# main_hall.net
KiCad netlist of a schematic drawn in Altium Designer
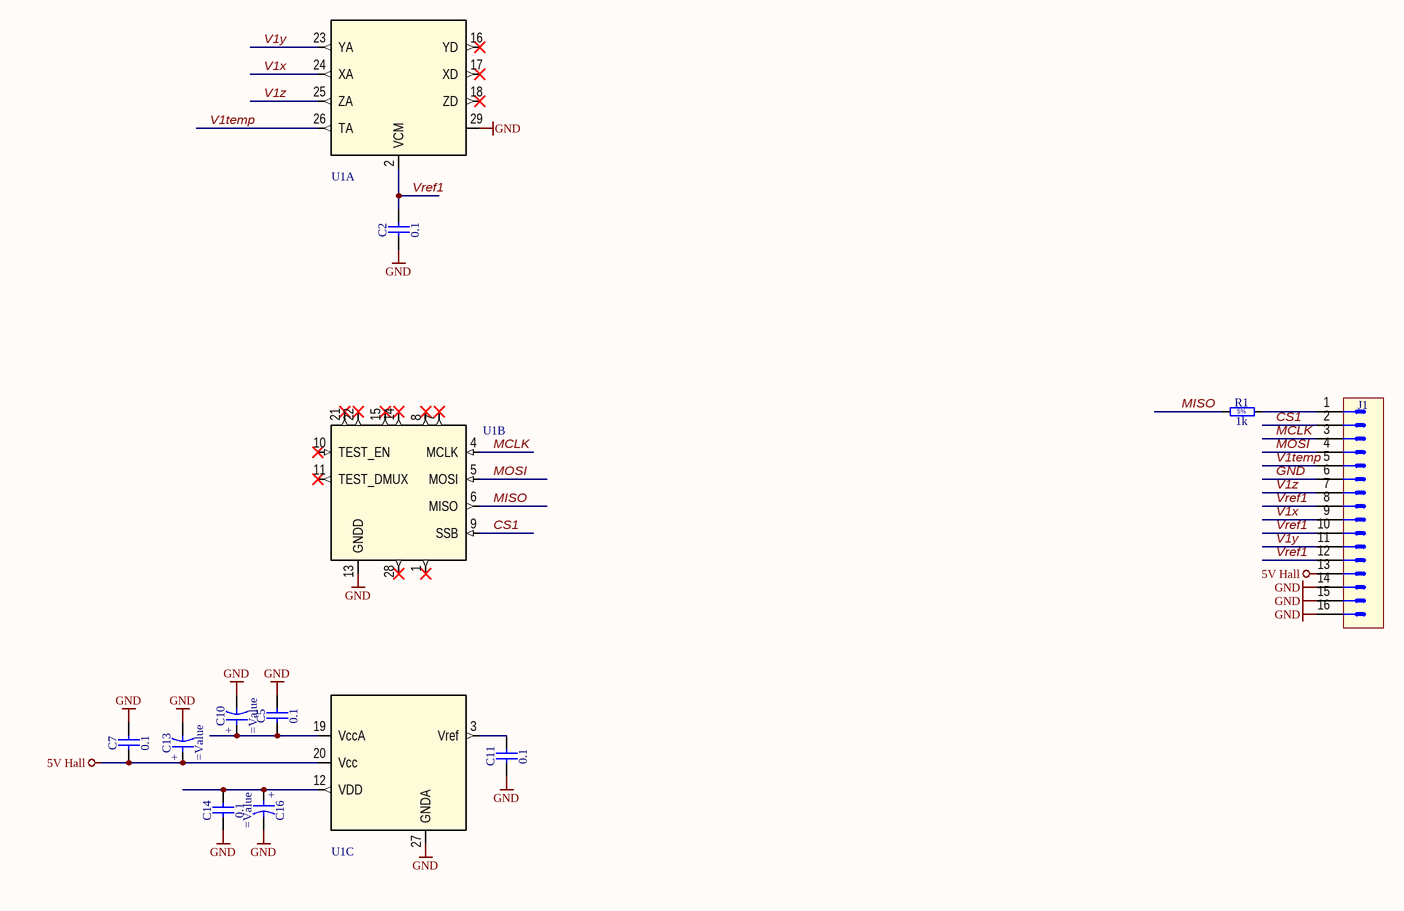
[diagram p0: main_hall.SchDoc]

(export (version "E")
  (design (tool "Eeschema 10.0.6"))
  (components
    (comp (ref "C2")
      (value "0.1")
      (footprint "CAPC3216X100N")
      (description "Non-polarised1206 capacitor")
      (libsource (lib "hall library") (part "Capacitor1206 - non polarized"))
    )
    (comp (ref "C5")
      (value "0.1")
      (footprint "CAPC3216X100N")
      (description "Non-polarised1206 capacitor")
      (libsource (lib "hall library") (part "Capacitor1206 - non polarized"))
    )
    (comp (ref "C7")
      (value "0.1")
      (footprint "CAPC3216X100N")
      (description "Non-polarised1206 capacitor")
      (libsource (lib "hall library") (part "Capacitor1206 - non polarized"))
    )
    (comp (ref "C10")
      (value "~")
      (footprint "hall library:CAPMP3528X120N")
      (description "Polarised capacitor")
      (libsource (lib "schematic_hall_library") (part "Capacitor - polarized"))
    )
    (comp (ref "C11")
      (value "0.1")
      (footprint "CAPC3216X100N")
      (description "Non-polarised1206 capacitor")
      (libsource (lib "hall library") (part "Capacitor1206 - non polarized"))
    )
    (comp (ref "C13")
      (value "~")
      (footprint "hall library:CAPMP3528X120N")
      (description "Polarised capacitor")
      (libsource (lib "schematic_hall_library") (part "Capacitor - polarized"))
    )
    (comp (ref "C14")
      (value "0.1")
      (footprint "CAPC3216X100N")
      (description "Non-polarised1206 capacitor")
      (libsource (lib "hall library") (part "Capacitor1206 - non polarized"))
    )
    (comp (ref "C16")
      (value "~")
      (footprint "hall library:CAPMP3528X120N")
      (description "Polarised capacitor")
      (libsource (lib "schematic_hall_library") (part "Capacitor - polarized"))
    )
    (comp (ref "J1")
      (value "~")
      (footprint "3M_N2516-5002RB")
      (description "Connector 16")
      (libsource (lib "hall library") (part "Connector 16"))
    )
    (comp (ref "R1")
      (value "1k")
      (footprint "footprint_hall_library:RESC2012X70N")
      (description "Resistor - 5%")
      (fields (field (name "TOLERANCE") "5%"))
      (libsource (lib "schematic_hall_library") (part "Resistor - 5%"))
    )
    (comp (ref "U1")
      (value "Hall sensor")
      (footprint "footprint_hall_library:QFN50P500X500X100-29N-S325")
      (description "SENM3Dx Vertical Hall Sensor")
      (libsource (lib "schematic_hall_library") (part "Hall sensor"))
    )
  )
  (nets
    (net (code "1") (name "/CS1") (class "Default")
      (node (ref "J1") (pin "2") (pinfunction "2_2") (pintype "passive"))
      (node (ref "U1") (pin "9") (pinfunction "SSB_9") (pintype "input"))
    )
    (net (code "2") (name "/MCLK") (class "Default")
      (node (ref "J1") (pin "3") (pinfunction "3_3") (pintype "passive"))
      (node (ref "U1") (pin "4") (pinfunction "MCLK_4") (pintype "input"))
    )
    (net (code "3") (name "/MISO") (class "Default")
      (node (ref "R1") (pin "1") (pinfunction "1_1") (pintype "passive"))
      (node (ref "U1") (pin "6") (pinfunction "MISO_6") (pintype "output"))
    )
    (net (code "4") (name "/MOSI") (class "Default")
      (node (ref "J1") (pin "4") (pinfunction "4_4") (pintype "passive"))
      (node (ref "U1") (pin "5") (pinfunction "MOSI_5") (pintype "input"))
    )
    (net (code "5") (name "/V1temp") (class "Default")
      (node (ref "J1") (pin "5") (pinfunction "5_5") (pintype "passive"))
      (node (ref "U1") (pin "26") (pinfunction "TA_26") (pintype "output"))
    )
    (net (code "6") (name "/V1x") (class "Default")
      (node (ref "J1") (pin "9") (pinfunction "9_9") (pintype "passive"))
      (node (ref "U1") (pin "24") (pinfunction "XA_24") (pintype "output"))
    )
    (net (code "7") (name "/V1y") (class "Default")
      (node (ref "J1") (pin "11") (pinfunction "11_11") (pintype "passive"))
      (node (ref "U1") (pin "23") (pinfunction "YA_23") (pintype "output"))
    )
    (net (code "8") (name "/V1z") (class "Default")
      (node (ref "J1") (pin "7") (pinfunction "7_7") (pintype "passive"))
      (node (ref "U1") (pin "25") (pinfunction "ZA_25") (pintype "output"))
    )
    (net (code "9") (name "/Vref1") (class "Default")
      (node (ref "C2") (pin "2") (pinfunction "2_2") (pintype "passive"))
      (node (ref "J1") (pin "10") (pinfunction "10_10") (pintype "passive"))
      (node (ref "J1") (pin "12") (pinfunction "12_12") (pintype "passive"))
      (node (ref "J1") (pin "8") (pinfunction "8_8") (pintype "passive"))
      (node (ref "U1") (pin "2") (pinfunction "VCM_2") (pintype "power_in"))
    )
    (net (code "10") (name "5V Hall") (class "Default")
      (node (ref "C13") (pin "1") (pinfunction "1_1") (pintype "passive"))
      (node (ref "C7") (pin "1") (pinfunction "1_1") (pintype "passive"))
      (node (ref "J1") (pin "13") (pinfunction "13_13") (pintype "passive"))
      (node (ref "U1") (pin "20") (pinfunction "Vcc_20") (pintype "power_in"))
    )
    (net (code "11") (name "GND") (class "Default")
      (node (ref "C10") (pin "2") (pinfunction "2_2") (pintype "passive"))
      (node (ref "C11") (pin "1") (pinfunction "1_1") (pintype "passive"))
      (node (ref "C13") (pin "2") (pinfunction "2_2") (pintype "passive"))
      (node (ref "C14") (pin "1") (pinfunction "1_1") (pintype "passive"))
      (node (ref "C16") (pin "2") (pinfunction "2_2") (pintype "passive"))
      (node (ref "C2") (pin "1") (pinfunction "1_1") (pintype "passive"))
      (node (ref "C5") (pin "2") (pinfunction "2_2") (pintype "passive"))
      (node (ref "C7") (pin "2") (pinfunction "2_2") (pintype "passive"))
      (node (ref "J1") (pin "14") (pinfunction "14_14") (pintype "passive"))
      (node (ref "J1") (pin "15") (pinfunction "15_15") (pintype "passive"))
      (node (ref "J1") (pin "16") (pinfunction "16_16") (pintype "passive"))
      (node (ref "J1") (pin "6") (pinfunction "6_6") (pintype "passive"))
      (node (ref "U1") (pin "13") (pinfunction "GNDD_13") (pintype "power_in"))
      (node (ref "U1") (pin "27") (pinfunction "GNDA_27") (pintype "power_in"))
      (node (ref "U1") (pin "29") (pinfunction "29_29") (pintype "passive"))
    )
    (net (code "12") (name "Net-(J1-Pad1)") (class "Default")
      (node (ref "J1") (pin "1") (pinfunction "1_1") (pintype "passive"))
      (node (ref "R1") (pin "2") (pinfunction "2_2") (pintype "passive"))
    )
    (net (code "13") (name "Net-(U1C-VDD)") (class "Default")
      (node (ref "C14") (pin "2") (pinfunction "2_2") (pintype "passive"))
      (node (ref "C16") (pin "1") (pinfunction "1_1") (pintype "passive"))
      (node (ref "U1") (pin "12") (pinfunction "VDD_12") (pintype "output"))
    )
    (net (code "14") (name "Net-(U1C-VccA)") (class "Default")
      (node (ref "C10") (pin "1") (pinfunction "1_1") (pintype "passive"))
      (node (ref "C5") (pin "1") (pinfunction "1_1") (pintype "passive"))
      (node (ref "U1") (pin "19") (pinfunction "VccA_19") (pintype "power_in"))
    )
    (net (code "15") (name "Net-(U1C-Vref)") (class "Default")
      (node (ref "C11") (pin "2") (pinfunction "2_2") (pintype "passive"))
      (node (ref "U1") (pin "3") (pinfunction "Vref_3") (pintype "output"))
    )
    (net (code "16") (name "unconnected-(U1-Pad1)") (class "Default")
      (node (ref "U1") (pin "1") (pintype "output+no_connect"))
    )
    (net (code "17") (name "unconnected-(U1-Pad7)") (class "Default")
      (node (ref "U1") (pin "7") (pintype "output+no_connect"))
    )
    (net (code "18") (name "unconnected-(U1-Pad8)") (class "Default")
      (node (ref "U1") (pin "8") (pintype "output+no_connect"))
    )
    (net (code "19") (name "unconnected-(U1-Pad14)") (class "Default")
      (node (ref "U1") (pin "14") (pintype "output+no_connect"))
    )
    (net (code "20") (name "unconnected-(U1-Pad15)") (class "Default")
      (node (ref "U1") (pin "15") (pintype "output+no_connect"))
    )
    (net (code "21") (name "unconnected-(U1-Pad21)") (class "Default")
      (node (ref "U1") (pin "21") (pintype "output+no_connect"))
    )
    (net (code "22") (name "unconnected-(U1-Pad22)") (class "Default")
      (node (ref "U1") (pin "22") (pintype "output+no_connect"))
    )
    (net (code "23") (name "unconnected-(U1-Pad28)") (class "Default")
      (node (ref "U1") (pin "28") (pintype "output+no_connect"))
    )
    (net (code "24") (name "unconnected-(U1A-XD-Pad17)") (class "Default")
      (node (ref "U1") (pin "17") (pinfunction "XD_17") (pintype "output+no_connect"))
    )
    (net (code "25") (name "unconnected-(U1A-YD-Pad16)") (class "Default")
      (node (ref "U1") (pin "16") (pinfunction "YD_16") (pintype "output+no_connect"))
    )
    (net (code "26") (name "unconnected-(U1A-ZD-Pad18)") (class "Default")
      (node (ref "U1") (pin "18") (pinfunction "ZD_18") (pintype "output+no_connect"))
    )
    (net (code "27") (name "unconnected-(U1B-TEST_DMUX-Pad11)") (class "Default")
      (node (ref "U1") (pin "11") (pinfunction "TEST_DMUX_11") (pintype "output+no_connect"))
    )
    (net (code "28") (name "unconnected-(U1B-TEST_EN-Pad10)") (class "Default")
      (node (ref "U1") (pin "10") (pinfunction "TEST_EN_10") (pintype "input+no_connect"))
    )
  )
)
